# Power.net
KiCad netlist of a schematic drawn in Altium Designer
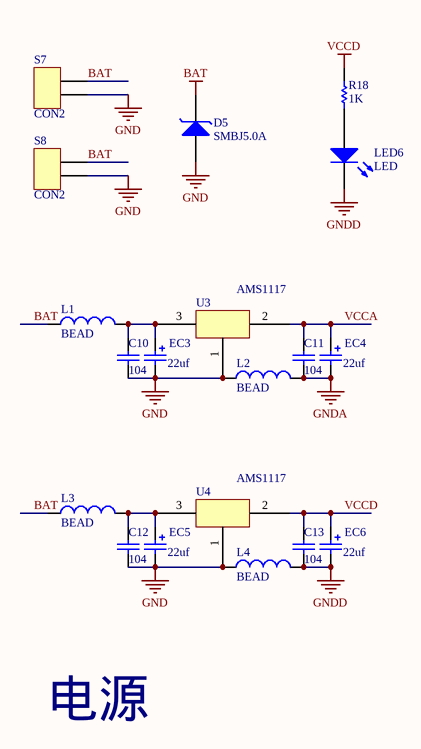
[diagram p0: Power.SchDoc]

(export (version "E")
  (design (tool "Eeschema 10.0.6"))
  (components
    (comp (ref "C10") (value "104") (footprint "0603") (libsource (lib "yezi_sch") (part "CAP")))
    (comp (ref "C11") (value "104") (footprint "0603") (libsource (lib "yezi_sch") (part "CAP")))
    (comp (ref "C12") (value "104") (footprint "0603") (libsource (lib "yezi_sch") (part "CAP")))
    (comp (ref "C13") (value "104") (footprint "0603") (libsource (lib "yezi_sch") (part "CAP")))
    (comp (ref "D5")
      (value "SMBJ5.0A")
      (footprint "DIOM4436X23N")
      (libsource (lib "yezi_sch") (part "SMBJ5.0A"))
    )
    (comp (ref "EC3") (value "22uf") (footprint "1206") (libsource (lib "yezi_sch") (part "EC")))
    (comp (ref "EC4") (value "22uf") (footprint "1206") (libsource (lib "yezi_sch") (part "EC")))
    (comp (ref "EC5") (value "22uf") (footprint "1206") (libsource (lib "yezi_sch") (part "EC")))
    (comp (ref "EC6") (value "22uf") (footprint "1206") (libsource (lib "yezi_sch") (part "EC")))
    (comp (ref "L1")
      (value "BEAD")
      (footprint "0805")
      (description "Inductor")
      (fields (field (name "PUBLISHER") "Altium Limited"))
      (libsource (lib "yezi_sch") (part "Inductor"))
    )
    (comp (ref "L2")
      (value "BEAD")
      (footprint "0805")
      (description "Inductor")
      (fields (field (name "PUBLISHER") "Altium Limited"))
      (libsource (lib "yezi_sch") (part "Inductor"))
    )
    (comp (ref "L3")
      (value "BEAD")
      (footprint "0805")
      (description "Inductor")
      (fields (field (name "PUBLISHER") "Altium Limited"))
      (libsource (lib "yezi_sch") (part "Inductor"))
    )
    (comp (ref "L4")
      (value "BEAD")
      (footprint "0805")
      (description "Inductor")
      (fields (field (name "PUBLISHER") "Altium Limited"))
      (libsource (lib "yezi_sch") (part "Inductor"))
    )
    (comp (ref "LED6") (value "LED") (footprint "0805") (libsource (lib "yezi_sch") (part "LED")))
    (comp (ref "R18") (value "1K") (footprint "0603") (libsource (lib "yezi_sch") (part "RES")))
    (comp (ref "S7") (value "CON2") (footprint "SIP2") (libsource (lib "yezi_sch") (part "CON2")))
    (comp (ref "S8") (value "CON2") (footprint "1206") (libsource (lib "yezi_sch") (part "CON2")))
    (comp (ref "U3") (value "AMS1117") (footprint "SOT223") (libsource (lib "yezi_sch") (part "AMS1117")))
    (comp (ref "U4") (value "AMS1117") (footprint "SOT223") (libsource (lib "yezi_sch") (part "AMS1117")))
  )
  (nets
    (net (code "1") (name "/VCCA") (class "Default")
      (node (ref "C11") (pin "1") (pinfunction "1_1") (pintype "passive"))
      (node (ref "EC4") (pin "1") (pinfunction "1_1") (pintype "passive"))
      (node (ref "U3") (pin "2") (pinfunction "2_2") (pintype "passive"))
    )
    (net (code "2") (name "BAT") (class "Default")
      (node (ref "D5") (pin "2") (pinfunction "K_2") (pintype "passive"))
      (node (ref "L1") (pin "1") (pinfunction "1_1") (pintype "passive"))
      (node (ref "L3") (pin "1") (pinfunction "1_1") (pintype "passive"))
      (node (ref "S7") (pin "1") (pinfunction "1_1") (pintype "passive"))
      (node (ref "S8") (pin "1") (pinfunction "1_1") (pintype "passive"))
    )
    (net (code "3") (name "GND") (class "Default")
      (node (ref "C10") (pin "2") (pinfunction "2_2") (pintype "passive"))
      (node (ref "C12") (pin "2") (pinfunction "2_2") (pintype "passive"))
      (node (ref "D5") (pin "1") (pinfunction "A_1") (pintype "passive"))
      (node (ref "EC3") (pin "2") (pinfunction "2_2") (pintype "passive"))
      (node (ref "EC5") (pin "2") (pinfunction "2_2") (pintype "passive"))
      (node (ref "L2") (pin "1") (pinfunction "1_1") (pintype "passive"))
      (node (ref "L4") (pin "1") (pinfunction "1_1") (pintype "passive"))
      (node (ref "S7") (pin "2") (pinfunction "2_2") (pintype "passive"))
      (node (ref "S8") (pin "2") (pinfunction "2_2") (pintype "passive"))
      (node (ref "U3") (pin "1") (pinfunction "1_1") (pintype "passive"))
      (node (ref "U4") (pin "1") (pinfunction "1_1") (pintype "passive"))
    )
    (net (code "4") (name "GNDA") (class "Default")
      (node (ref "C11") (pin "2") (pinfunction "2_2") (pintype "passive"))
      (node (ref "EC4") (pin "2") (pinfunction "2_2") (pintype "passive"))
      (node (ref "L2") (pin "2") (pinfunction "2_2") (pintype "passive"))
    )
    (net (code "5") (name "GNDD") (class "Default")
      (node (ref "C13") (pin "2") (pinfunction "2_2") (pintype "passive"))
      (node (ref "EC6") (pin "2") (pinfunction "2_2") (pintype "passive"))
      (node (ref "L4") (pin "2") (pinfunction "2_2") (pintype "passive"))
      (node (ref "LED6") (pin "2") (pinfunction "K_2") (pintype "passive"))
    )
    (net (code "6") (name "Net-(C10-Pad1)") (class "Default")
      (node (ref "C10") (pin "1") (pinfunction "1_1") (pintype "passive"))
      (node (ref "EC3") (pin "1") (pinfunction "1_1") (pintype "passive"))
      (node (ref "L1") (pin "2") (pinfunction "2_2") (pintype "passive"))
      (node (ref "U3") (pin "3") (pinfunction "3_3") (pintype "passive"))
    )
    (net (code "7") (name "Net-(C12-Pad1)") (class "Default")
      (node (ref "C12") (pin "1") (pinfunction "1_1") (pintype "passive"))
      (node (ref "EC5") (pin "1") (pinfunction "1_1") (pintype "passive"))
      (node (ref "L3") (pin "2") (pinfunction "2_2") (pintype "passive"))
      (node (ref "U4") (pin "3") (pinfunction "3_3") (pintype "passive"))
    )
    (net (code "8") (name "Net-(LED6-A)") (class "Default")
      (node (ref "LED6") (pin "1") (pinfunction "A_1") (pintype "passive"))
      (node (ref "R18") (pin "2") (pinfunction "2_2") (pintype "passive"))
    )
    (net (code "9") (name "VCCD") (class "Default")
      (node (ref "C13") (pin "1") (pinfunction "1_1") (pintype "passive"))
      (node (ref "EC6") (pin "1") (pinfunction "1_1") (pintype "passive"))
      (node (ref "R18") (pin "1") (pinfunction "1_1") (pintype "passive"))
      (node (ref "U4") (pin "2") (pinfunction "2_2") (pintype "passive"))
    )
    (net (code "10") (name "unconnected-(U3-Pad4)") (class "Default")
      (node (ref "U3") (pin "4") (pinfunction "4_4") (pintype "passive"))
    )
    (net (code "11") (name "unconnected-(U4-Pad4)") (class "Default")
      (node (ref "U4") (pin "4") (pinfunction "4_4") (pintype "passive"))
    )
  )
)
